# design.net
KiCad netlist of a schematic drawn in Altium Designer
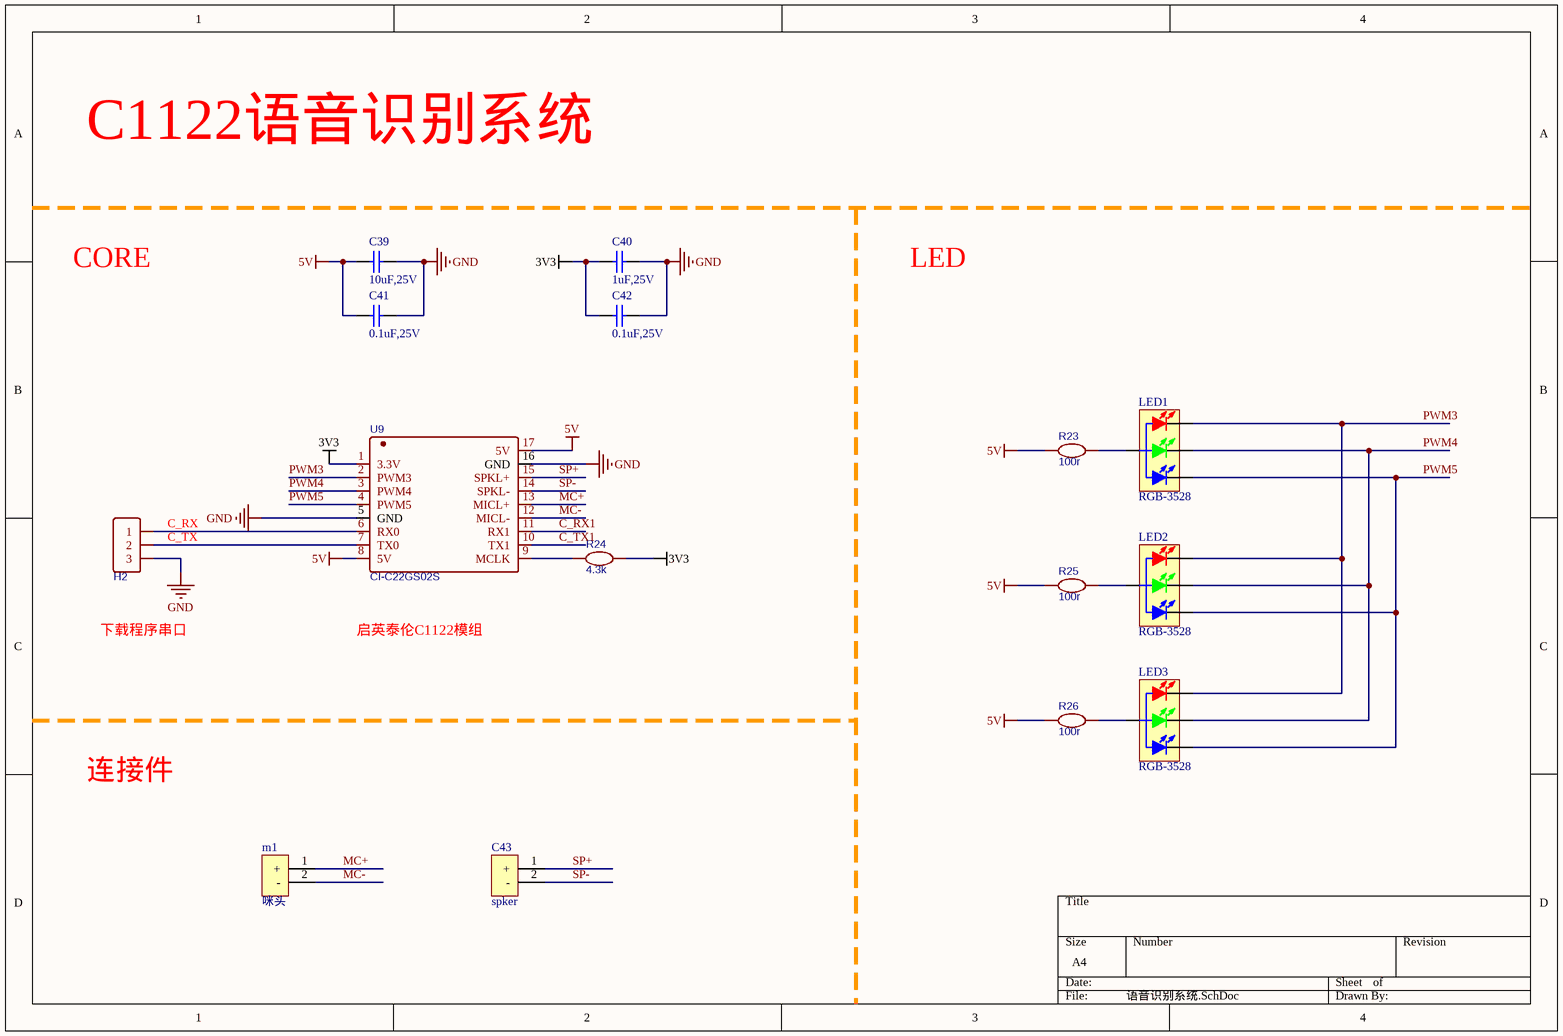
[diagram p0: 语音识别系统.SchDoc]

(export (version "E")
  (design (tool "Eeschema 10.0.6"))
  (components
    (comp (ref "C39")
      (value "10uF,25V")
      (footprint "0402_C")
      (description "贴片电容")
      (fields (field (name "PART NUMBER") "T_Cap_0603_0.1uF_25V_X5R") (field (name "TOLERANCE") "10%"))
      (libsource (lib "Database_Library") (part "Cap"))
    )
    (comp (ref "C40")
      (value "1uF,25V")
      (footprint "0402_C")
      (description "贴片电容")
      (fields (field (name "PART NUMBER") "T_Cap_0603_0.1uF_25V_X5R") (field (name "TOLERANCE") "10%"))
      (libsource (lib "Database_Library") (part "Cap"))
    )
    (comp (ref "C41")
      (value "0.1uF,25V")
      (footprint "0402_C")
      (description "贴片电容")
      (fields (field (name "PART NUMBER") "T_Cap_0603_0.1uF_25V_X5R") (field (name "TOLERANCE") "10%"))
      (libsource (lib "Database_Library") (part "Cap"))
    )
    (comp (ref "C42")
      (value "0.1uF,25V")
      (footprint "0402_C")
      (description "贴片电容")
      (fields (field (name "PART NUMBER") "T_Cap_0603_0.1uF_25V_X5R") (field (name "TOLERANCE") "10%"))
      (libsource (lib "Database_Library") (part "Cap"))
    )
    (comp (ref "C43") (value "spker") (footprint "XH2.54A-2") (libsource (lib "Schlib_PICO") (part "SPK")))
    (comp (ref "H2")
      (value "HDR-F-2.54_1x3")
      (footprint "XH2.54A-3")
      (fields (field (name "BOM_SUPPLIER PART") "C146690") (field (name "CONTRIBUTOR") "LCEDA_Lib"))
      (libsource (lib "altium-import") (part "root_0_mirrored_HDR-F-2.54_1x3_"))
    )
    (comp (ref "LED1")
      (value "RGB-3528")
      (footprint "LED-TH_4P-BD6.9-P1.27-R")
      (description "三基色LED")
      (fields (field (name "版权归属") "源创客"))
      (libsource (lib "Schlib_PICO") (part "LED-RGB-3528"))
    )
    (comp (ref "LED2")
      (value "RGB-3528")
      (footprint "LED-TH_4P-BD6.9-P1.27-R")
      (description "三基色LED")
      (fields (field (name "版权归属") "源创客"))
      (libsource (lib "Schlib_PICO") (part "LED-RGB-3528"))
    )
    (comp (ref "LED3")
      (value "RGB-3528")
      (footprint "LED-TH_4P-BD6.9-P1.27-R")
      (description "三基色LED")
      (fields (field (name "版权归属") "源创客"))
      (libsource (lib "Schlib_PICO") (part "LED-RGB-3528"))
    )
    (comp (ref "m1")
      (value "咪头")
      (footprint "MIC-TH_BD6.0-P1.90-D0.4-L-RD")
      (libsource (lib "Schlib_PICO") (part "mic"))
    )
    (comp (ref "R23")
      (value "100r")
      (footprint "0402_R")
      (fields (field (name "CONTRIBUTOR") "LCEDA_Lib"))
      (libsource (lib "altium-import") (part "root_2_100k_"))
    )
    (comp (ref "R24")
      (value "4.3k")
      (footprint "0402_R")
      (fields (field (name "CONTRIBUTOR") "LCEDA_Lib"))
      (libsource (lib "altium-import") (part "root_2_100k_"))
    )
    (comp (ref "R25")
      (value "100r")
      (footprint "0402_R")
      (fields (field (name "CONTRIBUTOR") "LCEDA_Lib"))
      (libsource (lib "altium-import") (part "root_2_100k_"))
    )
    (comp (ref "R26")
      (value "100r")
      (footprint "0402_R")
      (fields (field (name "CONTRIBUTOR") "LCEDA_Lib"))
      (libsource (lib "altium-import") (part "root_2_100k_"))
    )
    (comp (ref "U9")
      (value "CI-C22GS02S")
      (footprint "SMD-17_L20.0-W1.80-CI-C22GS02S")
      (fields (field (name "BOM_SUPPLIER PART") "C2759836") (field (name "CONTRIBUTOR") "LCSC"))
      (libsource (lib "Schlib_PICO") (part "CI-C22GS02S"))
    )
  )
  (nets
    (net (code "1") (name "/C_RX1") (class "Default")
      (node (ref "U9") (pin "11") (pinfunction "RX1_11") (pintype "passive"))
    )
    (net (code "2") (name "/C_TX1") (class "Default")
      (node (ref "U9") (pin "10") (pinfunction "TX1_10") (pintype "passive"))
    )
    (net (code "3") (name "/MC+") (class "Default")
      (node (ref "U9") (pin "13") (pinfunction "MICL+_13") (pintype "passive"))
      (node (ref "m1") (pin "1") (pinfunction "+_1") (pintype "passive"))
    )
    (net (code "4") (name "/MC-") (class "Default")
      (node (ref "U9") (pin "12") (pinfunction "MICL-_12") (pintype "passive"))
      (node (ref "m1") (pin "2") (pinfunction "-_2") (pintype "passive"))
    )
    (net (code "5") (name "/PWM3") (class "Default")
      (node (ref "LED1") (pin "1") (pinfunction "RED_K_1") (pintype "passive"))
      (node (ref "LED2") (pin "1") (pinfunction "RED_K_1") (pintype "passive"))
      (node (ref "LED3") (pin "1") (pinfunction "RED_K_1") (pintype "passive"))
      (node (ref "U9") (pin "2") (pinfunction "PWM3_2") (pintype "passive"))
    )
    (net (code "6") (name "/PWM4") (class "Default")
      (node (ref "LED1") (pin "3") (pinfunction "GREEN_K_3") (pintype "passive"))
      (node (ref "LED2") (pin "3") (pinfunction "GREEN_K_3") (pintype "passive"))
      (node (ref "LED3") (pin "3") (pinfunction "GREEN_K_3") (pintype "passive"))
      (node (ref "U9") (pin "3") (pinfunction "PWM4_3") (pintype "passive"))
    )
    (net (code "7") (name "/PWM5") (class "Default")
      (node (ref "LED1") (pin "4") (pinfunction "BULE_K_4") (pintype "passive"))
      (node (ref "LED2") (pin "4") (pinfunction "BULE_K_4") (pintype "passive"))
      (node (ref "LED3") (pin "4") (pinfunction "BULE_K_4") (pintype "passive"))
      (node (ref "U9") (pin "4") (pinfunction "PWM5_4") (pintype "passive"))
    )
    (net (code "8") (name "/SP+") (class "Default")
      (node (ref "C43") (pin "1") (pinfunction "+_1") (pintype "passive"))
      (node (ref "U9") (pin "15") (pinfunction "SPKL+_15") (pintype "passive"))
    )
    (net (code "9") (name "/SP-") (class "Default")
      (node (ref "C43") (pin "2") (pinfunction "-_2") (pintype "passive"))
      (node (ref "U9") (pin "14") (pinfunction "SPKL-_14") (pintype "passive"))
    )
    (net (code "10") (name "3V3") (class "Default")
      (node (ref "C40") (pin "1") (pinfunction "1_1") (pintype "passive"))
      (node (ref "C42") (pin "1") (pinfunction "1_1") (pintype "passive"))
      (node (ref "R24") (pin "1") (pinfunction "1_1") (pintype "passive"))
      (node (ref "U9") (pin "1") (pinfunction "3.3V_1") (pintype "passive"))
    )
    (net (code "11") (name "5V") (class "Default")
      (node (ref "C39") (pin "1") (pinfunction "1_1") (pintype "passive"))
      (node (ref "C41") (pin "1") (pinfunction "1_1") (pintype "passive"))
      (node (ref "R23") (pin "2") (pinfunction "2_2") (pintype "passive"))
      (node (ref "R25") (pin "2") (pinfunction "2_2") (pintype "passive"))
      (node (ref "R26") (pin "2") (pinfunction "2_2") (pintype "passive"))
      (node (ref "U9") (pin "17") (pinfunction "5V_17") (pintype "passive"))
      (node (ref "U9") (pin "8") (pinfunction "5V_8") (pintype "passive"))
    )
    (net (code "12") (name "GND") (class "Default")
      (node (ref "C39") (pin "2") (pinfunction "2_2") (pintype "passive"))
      (node (ref "C40") (pin "2") (pinfunction "2_2") (pintype "passive"))
      (node (ref "C41") (pin "2") (pinfunction "2_2") (pintype "passive"))
      (node (ref "C42") (pin "2") (pinfunction "2_2") (pintype "passive"))
      (node (ref "H2") (pin "3") (pinfunction "3_3") (pintype "passive"))
      (node (ref "U9") (pin "16") (pinfunction "GND_16") (pintype "passive"))
      (node (ref "U9") (pin "5") (pinfunction "GND_5") (pintype "passive"))
    )
    (net (code "13") (name "Net-(LED1-A)") (class "Default")
      (node (ref "LED1") (pin "2") (pinfunction "A_2") (pintype "passive"))
      (node (ref "R23") (pin "1") (pinfunction "1_1") (pintype "passive"))
    )
    (net (code "14") (name "Net-(LED2-A)") (class "Default")
      (node (ref "LED2") (pin "2") (pinfunction "A_2") (pintype "passive"))
      (node (ref "R25") (pin "1") (pinfunction "1_1") (pintype "passive"))
    )
    (net (code "15") (name "Net-(LED3-A)") (class "Default")
      (node (ref "LED3") (pin "2") (pinfunction "A_2") (pintype "passive"))
      (node (ref "R26") (pin "1") (pinfunction "1_1") (pintype "passive"))
    )
    (net (code "16") (name "Net-(U9-MCLK)") (class "Default")
      (node (ref "R24") (pin "2") (pinfunction "2_2") (pintype "passive"))
      (node (ref "U9") (pin "9") (pinfunction "MCLK_9") (pintype "passive"))
    )
    (net (code "17") (name "Net-(U9-RX0)") (class "Default")
      (node (ref "H2") (pin "1") (pinfunction "1_1") (pintype "passive"))
      (node (ref "U9") (pin "6") (pinfunction "RX0_6") (pintype "passive"))
    )
    (net (code "18") (name "Net-(U9-TX0)") (class "Default")
      (node (ref "H2") (pin "2") (pinfunction "2_2") (pintype "passive"))
      (node (ref "U9") (pin "7") (pinfunction "TX0_7") (pintype "passive"))
    )
  )
)
